# LEDs.net
KiCad netlist of a schematic drawn in Altium Designer
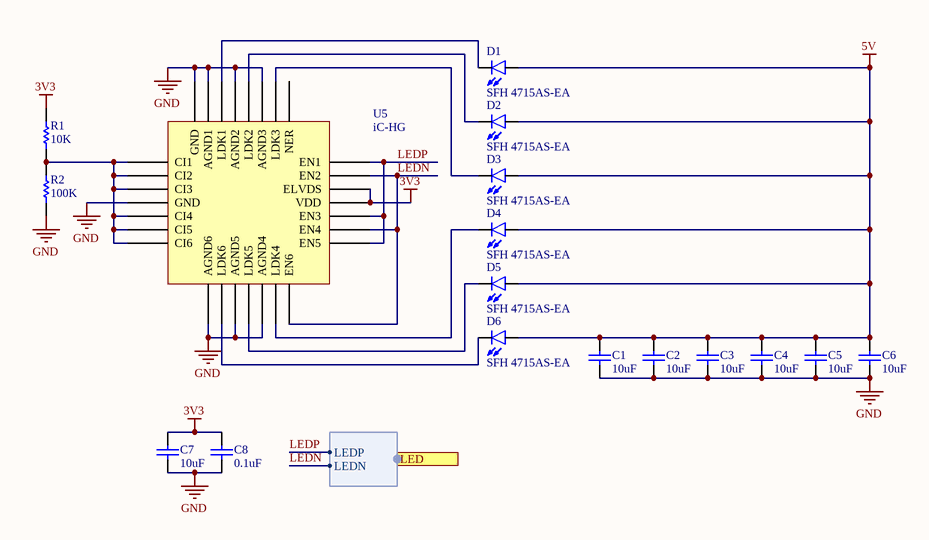
[diagram p0: LEDs.SchDoc]

(export (version "E")
  (design (tool "Eeschema 10.0.6"))
  (components
    (comp (ref "C1")
      (value "10uF")
      (footprint "C0402[1005X55]")
      (description "10uF 6.3V 20% 0402 (1005 Metric)")
      (fields (field (name "PARTNUMBER") "GRM155R60J106ME44D") (field (name "MANUFACTURER") "Murata"))
      (libsource (lib "Capacitors") (part "CAP_10uF_6.3V_0402_20%"))
    )
    (comp (ref "C2")
      (value "10uF")
      (footprint "C0402[1005X55]")
      (description "10uF 6.3V 20% 0402 (1005 Metric)")
      (fields (field (name "PARTNUMBER") "GRM155R60J106ME44D") (field (name "MANUFACTURER") "Murata"))
      (libsource (lib "Capacitors") (part "CAP_10uF_6.3V_0402_20%"))
    )
    (comp (ref "C3")
      (value "10uF")
      (footprint "C0402[1005X55]")
      (description "10uF 6.3V 20% 0402 (1005 Metric)")
      (fields (field (name "PARTNUMBER") "GRM155R60J106ME44D") (field (name "MANUFACTURER") "Murata"))
      (libsource (lib "Capacitors") (part "CAP_10uF_6.3V_0402_20%"))
    )
    (comp (ref "C4")
      (value "10uF")
      (footprint "C0402[1005X55]")
      (description "10uF 6.3V 20% 0402 (1005 Metric)")
      (fields (field (name "PARTNUMBER") "GRM155R60J106ME44D") (field (name "MANUFACTURER") "Murata"))
      (libsource (lib "Capacitors") (part "CAP_10uF_6.3V_0402_20%"))
    )
    (comp (ref "C5")
      (value "10uF")
      (footprint "C0402[1005X55]")
      (description "10uF 6.3V 20% 0402 (1005 Metric)")
      (fields (field (name "PARTNUMBER") "GRM155R60J106ME44D") (field (name "MANUFACTURER") "Murata"))
      (libsource (lib "Capacitors") (part "CAP_10uF_6.3V_0402_20%"))
    )
    (comp (ref "C6")
      (value "10uF")
      (footprint "C0402[1005X55]")
      (description "10uF 6.3V 20% 0402 (1005 Metric)")
      (fields (field (name "PARTNUMBER") "GRM155R60J106ME44D") (field (name "MANUFACTURER") "Murata"))
      (libsource (lib "Capacitors") (part "CAP_10uF_6.3V_0402_20%"))
    )
    (comp (ref "C7")
      (value "10uF")
      (footprint "C0402[1005X55]")
      (description "10uF 6.3V 20% 0402 (1005 Metric)")
      (fields (field (name "PARTNUMBER") "GRM155R60J106ME44D") (field (name "MANUFACTURER") "Murata"))
      (libsource (lib "Capacitors") (part "CAP_10uF_6.3V_0402_20%"))
    )
    (comp (ref "C8")
      (value "0.1uF")
      (footprint "C0402[1005X55]")
      (description "0.1uF 6.3V 10% 0402 (1005 Metric)")
      (fields (field (name "PARTNUMBER") "GRM155R70J104KA01D") (field (name "MANUFACTURER") "Murata"))
      (libsource (lib "Capacitors") (part "CAP_0.1uF_6.3V_0402_10%"))
    )
    (comp (ref "D1")
      (value "SFH 4715AS-EA")
      (footprint "SFH 4715AS")
      (fields (field (name "MANUFACTURER") "Osram"))
      (libsource (lib "LEDs") (part "SFH 4715AS-EA"))
    )
    (comp (ref "D2")
      (value "SFH 4715AS-EA")
      (footprint "SFH 4715AS")
      (fields (field (name "MANUFACTURER") "Osram"))
      (libsource (lib "LEDs") (part "SFH 4715AS-EA"))
    )
    (comp (ref "D3")
      (value "SFH 4715AS-EA")
      (footprint "SFH 4715AS")
      (fields (field (name "MANUFACTURER") "Osram"))
      (libsource (lib "LEDs") (part "SFH 4715AS-EA"))
    )
    (comp (ref "D4")
      (value "SFH 4715AS-EA")
      (footprint "SFH 4715AS")
      (fields (field (name "MANUFACTURER") "Osram"))
      (libsource (lib "LEDs") (part "SFH 4715AS-EA"))
    )
    (comp (ref "D5")
      (value "SFH 4715AS-EA")
      (footprint "SFH 4715AS")
      (fields (field (name "MANUFACTURER") "Osram"))
      (libsource (lib "LEDs") (part "SFH 4715AS-EA"))
    )
    (comp (ref "D6")
      (value "SFH 4715AS-EA")
      (footprint "SFH 4715AS")
      (fields (field (name "MANUFACTURER") "Osram"))
      (libsource (lib "LEDs") (part "SFH 4715AS-EA"))
    )
    (comp (ref "R1")
      (value "10K")
      (footprint "R0402[1005]")
      (description "10K 0.063W 1% 0402 (1005 Metric)")
      (fields (field (name "MANUFACTURER") "KOA Speer") (field (name "PARTNUMBER") "RK73H1ETTP1002F"))
      (libsource (lib "Resistors") (part "RES_10K_0402_1%"))
    )
    (comp (ref "R2")
      (value "100K")
      (footprint "R0402[1005]")
      (description "100K 0.063W 1% 0402 (1005 Metric)")
      (fields (field (name "MANUFACTURER") "KOA Speer") (field (name "PARTNUMBER") "RK73H1ETTP1003F"))
      (libsource (lib "Resistors") (part "RES_100K_0402_1%"))
    )
    (comp (ref "U5")
      (value "iC-HG")
      (footprint "QFN-28")
      (fields (field (name "PARTNUMBER") "iC-HG QFN28-5x5") (field (name "MANUFACTURER") "iC-Haus"))
      (libsource (lib "ICs") (part "iC-HG QFN28-5x5"))
    )
  )
  (nets
    (net (code "2") (name "/LEDN") (class "Default")
      (node (ref "U5") (pin "14") (pinfunction "EN6_14") (pintype "passive"))
      (node (ref "U5") (pin "16") (pinfunction "EN4_16") (pintype "passive"))
      (node (ref "U5") (pin "20") (pinfunction "EN2_20") (pintype "passive"))
    )
    (net (code "3") (name "/LEDP") (class "Default")
      (node (ref "U5") (pin "15") (pinfunction "EN5_15") (pintype "passive"))
      (node (ref "U5") (pin "17") (pinfunction "EN3_17") (pintype "passive"))
      (node (ref "U5") (pin "21") (pinfunction "EN1_21") (pintype "passive"))
    )
    (net (code "5") (name "3V3") (class "Default")
      (node (ref "C7") (pin "2") (pinfunction "2_2") (pintype "passive"))
      (node (ref "C8") (pin "2") (pinfunction "2_2") (pintype "passive"))
      (node (ref "R1") (pin "2") (pinfunction "2_2") (pintype "passive"))
      (node (ref "U5") (pin "18") (pinfunction "VDD_18") (pintype "passive"))
      (node (ref "U5") (pin "19") (pinfunction "ELVDS_19") (pintype "passive"))
    )
    (net (code "6") (name "5V") (class "Default")
      (node (ref "C1") (pin "2") (pinfunction "2_2") (pintype "passive"))
      (node (ref "C2") (pin "2") (pinfunction "2_2") (pintype "passive"))
      (node (ref "C3") (pin "2") (pinfunction "2_2") (pintype "passive"))
      (node (ref "C4") (pin "2") (pinfunction "2_2") (pintype "passive"))
      (node (ref "C5") (pin "2") (pinfunction "2_2") (pintype "passive"))
      (node (ref "C6") (pin "2") (pinfunction "2_2") (pintype "passive"))
      (node (ref "D1") (pin "A") (pinfunction "A_A") (pintype "passive"))
      (node (ref "D2") (pin "A") (pinfunction "A_A") (pintype "passive"))
      (node (ref "D3") (pin "A") (pinfunction "A_A") (pintype "passive"))
      (node (ref "D4") (pin "A") (pinfunction "A_A") (pintype "passive"))
      (node (ref "D5") (pin "A") (pinfunction "A_A") (pintype "passive"))
      (node (ref "D6") (pin "A") (pinfunction "A_A") (pintype "passive"))
    )
    (net (code "7") (name "GND") (class "Default")
      (node (ref "C1") (pin "1") (pinfunction "1_1") (pintype "passive"))
      (node (ref "C2") (pin "1") (pinfunction "1_1") (pintype "passive"))
      (node (ref "C3") (pin "1") (pinfunction "1_1") (pintype "passive"))
      (node (ref "C4") (pin "1") (pinfunction "1_1") (pintype "passive"))
      (node (ref "C5") (pin "1") (pinfunction "1_1") (pintype "passive"))
      (node (ref "C6") (pin "1") (pinfunction "1_1") (pintype "passive"))
      (node (ref "C7") (pin "1") (pinfunction "1_1") (pintype "passive"))
      (node (ref "C8") (pin "1") (pinfunction "1_1") (pintype "passive"))
      (node (ref "R2") (pin "1") (pinfunction "1_1") (pintype "passive"))
      (node (ref "U5") (pin "10") (pinfunction "AGND5_10") (pintype "passive"))
      (node (ref "U5") (pin "12") (pinfunction "AGND4_12") (pintype "passive"))
      (node (ref "U5") (pin "24") (pinfunction "AGND3_24") (pintype "passive"))
      (node (ref "U5") (pin "26") (pinfunction "AGND2_26") (pintype "passive"))
      (node (ref "U5") (pin "28") (pinfunction "AGND1_28") (pintype "passive"))
      (node (ref "U5") (pin "29") (pinfunction "GND_29") (pintype "passive"))
      (node (ref "U5") (pin "4") (pinfunction "GND_4") (pintype "passive"))
      (node (ref "U5") (pin "8") (pinfunction "AGND6_8") (pintype "passive"))
    )
    (net (code "8") (name "Net-(U5-CI1)") (class "Default")
      (node (ref "R1") (pin "1") (pinfunction "1_1") (pintype "passive"))
      (node (ref "R2") (pin "2") (pinfunction "2_2") (pintype "passive"))
      (node (ref "U5") (pin "1") (pinfunction "CI1_1") (pintype "passive"))
      (node (ref "U5") (pin "2") (pinfunction "CI2_2") (pintype "passive"))
      (node (ref "U5") (pin "3") (pinfunction "CI3_3") (pintype "passive"))
      (node (ref "U5") (pin "5") (pinfunction "CI4_5") (pintype "passive"))
      (node (ref "U5") (pin "6") (pinfunction "CI5_6") (pintype "passive"))
      (node (ref "U5") (pin "7") (pinfunction "CI6_7") (pintype "passive"))
    )
    (net (code "9") (name "Net-(U5-LDK1)") (class "Default")
      (node (ref "D1") (pin "C") (pinfunction "C_C") (pintype "passive"))
      (node (ref "U5") (pin "27") (pinfunction "LDK1_27") (pintype "passive"))
    )
    (net (code "10") (name "Net-(U5-LDK2)") (class "Default")
      (node (ref "D2") (pin "C") (pinfunction "C_C") (pintype "passive"))
      (node (ref "U5") (pin "25") (pinfunction "LDK2_25") (pintype "passive"))
    )
    (net (code "11") (name "Net-(U5-LDK3)") (class "Default")
      (node (ref "D3") (pin "C") (pinfunction "C_C") (pintype "passive"))
      (node (ref "U5") (pin "23") (pinfunction "LDK3_23") (pintype "passive"))
    )
    (net (code "12") (name "Net-(U5-LDK4)") (class "Default")
      (node (ref "D4") (pin "C") (pinfunction "C_C") (pintype "passive"))
      (node (ref "U5") (pin "13") (pinfunction "LDK4_13") (pintype "passive"))
    )
    (net (code "13") (name "Net-(U5-LDK5)") (class "Default")
      (node (ref "D5") (pin "C") (pinfunction "C_C") (pintype "passive"))
      (node (ref "U5") (pin "11") (pinfunction "LDK5_11") (pintype "passive"))
    )
    (net (code "14") (name "Net-(U5-LDK6)") (class "Default")
      (node (ref "D6") (pin "C") (pinfunction "C_C") (pintype "passive"))
      (node (ref "U5") (pin "9") (pinfunction "LDK6_9") (pintype "passive"))
    )
    (net (code "15") (name "unconnected-(U5-NER-Pad22)") (class "Default")
      (node (ref "U5") (pin "22") (pinfunction "NER_22") (pintype "passive"))
    )
  )
)
